# WiFi_SCH.net
KiCad netlist of a schematic drawn in Altium Designer
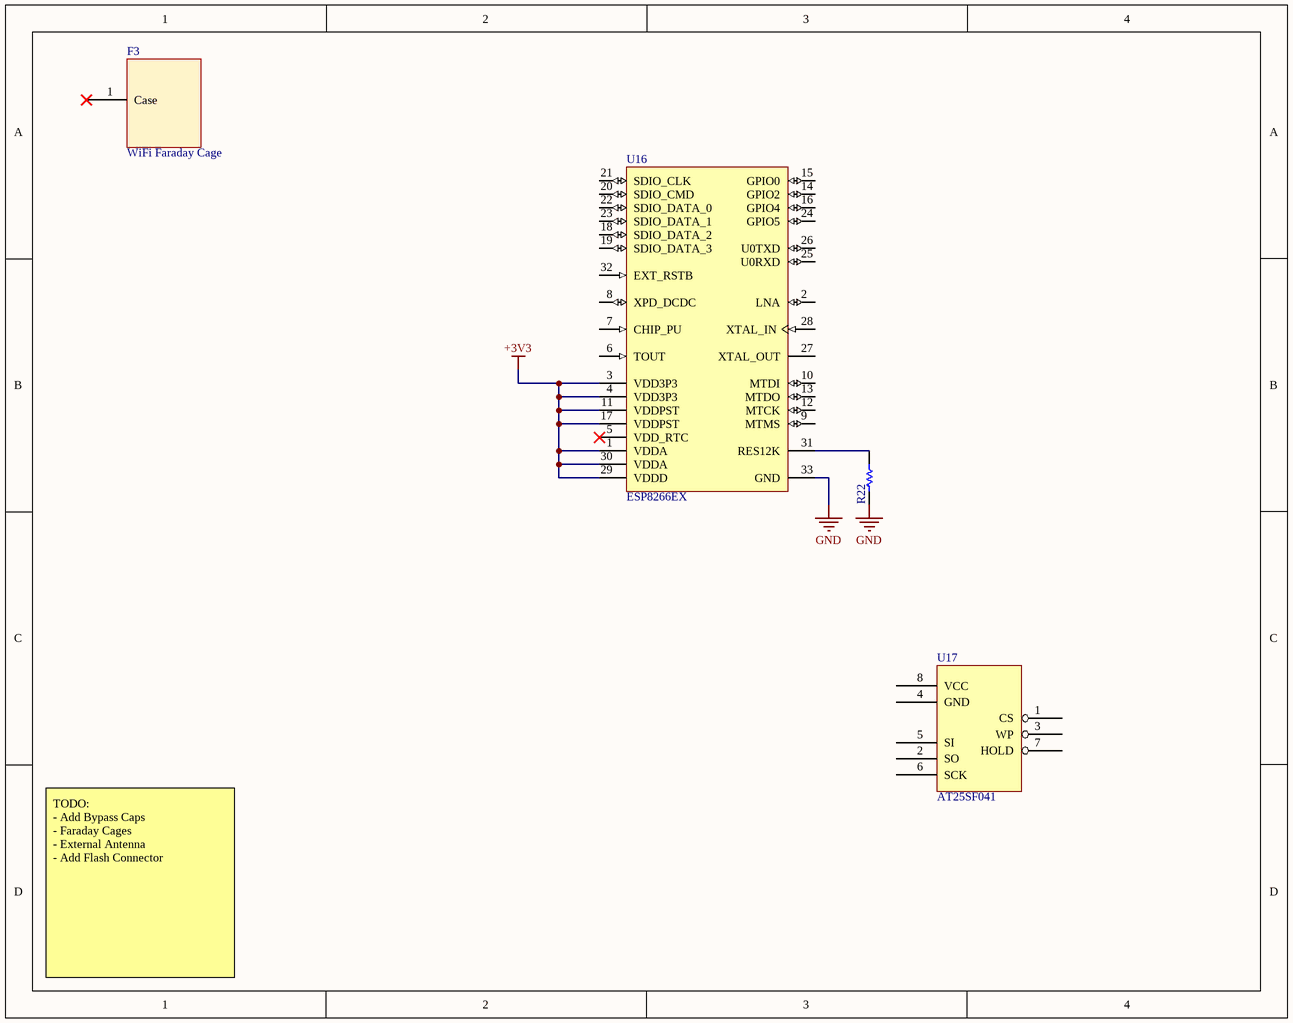
[diagram p0: WiFi_SCH.SchDoc]

(export (version "E")
  (design (tool "Eeschema 10.0.6"))
  (components
    (comp (ref "F3") (value "WiFi Faraday Cage") (libsource (lib "Copter") (part "FARADAY_CAGE")))
    (comp (ref "R22")
      (value "RES-2")
      (footprint "RES 0402")
      (fields (field (name "TOLERANCE") "1%"))
      (libsource (lib "Copter") (part "RES"))
    )
    (comp (ref "U16")
      (value "ESP8266EX")
      (footprint "ESFS-QFN-32_L")
      (description "Low-Power, Highly-Integrated Wi-Fi Solution, 2.5 to 3.6 V, 80 mA, -40 to 125 degC, 32-Pin QFN")
      (fields (field (name "MANUFACTURER") "Espressif Systems"))
      (libsource (lib "Altium Content Vault") (part "ESFS-ESP8266EX-32"))
    )
    (comp (ref "U17")
      (value "AT25SF041")
      (footprint "SOIC127P600X175-8N")
      (description "IC FLASH 4M SPI 104MHZ 8SOIC")
      (libsource (lib "Copter") (part "AT25SF041"))
    )
  )
  (nets
    (net (code "1") (name "+3V3") (class "Default")
      (node (ref "U16") (pin "1") (pinfunction "VDDA_1") (pintype "power_in"))
      (node (ref "U16") (pin "11") (pinfunction "VDDPST_11") (pintype "power_in"))
      (node (ref "U16") (pin "17") (pinfunction "VDDPST_17") (pintype "power_in"))
      (node (ref "U16") (pin "29") (pinfunction "VDDD_29") (pintype "power_in"))
      (node (ref "U16") (pin "3") (pinfunction "VDD3P3_3") (pintype "power_in"))
      (node (ref "U16") (pin "30") (pinfunction "VDDA_30") (pintype "power_in"))
      (node (ref "U16") (pin "4") (pinfunction "VDD3P3_4") (pintype "power_in"))
    )
    (net (code "2") (name "GND") (class "Default")
      (node (ref "R22") (pin "1") (pinfunction "1_1") (pintype "passive"))
      (node (ref "U16") (pin "33") (pinfunction "GND_33") (pintype "power_in"))
    )
    (net (code "3") (name "Net-(U16-RES12K)") (class "Default")
      (node (ref "R22") (pin "2") (pinfunction "2_2") (pintype "passive"))
      (node (ref "U16") (pin "31") (pinfunction "RES12K_31") (pintype "passive"))
    )
    (net (code "4") (name "unconnected-(F3-Case-Pad1)") (class "Default")
      (node (ref "F3") (pin "1") (pinfunction "Case_1") (pintype "passive+no_connect"))
    )
    (net (code "5") (name "unconnected-(U16-CHIP_PU-Pad7)") (class "Default")
      (node (ref "U16") (pin "7") (pinfunction "CHIP_PU_7") (pintype "input"))
    )
    (net (code "6") (name "unconnected-(U16-EXT_RSTB-Pad32)") (class "Default")
      (node (ref "U16") (pin "32") (pinfunction "EXT_RSTB_32") (pintype "input"))
    )
    (net (code "7") (name "unconnected-(U16-GPIO0-Pad15)") (class "Default")
      (node (ref "U16") (pin "15") (pinfunction "GPIO0_15") (pintype "bidirectional"))
    )
    (net (code "8") (name "unconnected-(U16-GPIO2-Pad14)") (class "Default")
      (node (ref "U16") (pin "14") (pinfunction "GPIO2_14") (pintype "bidirectional"))
    )
    (net (code "9") (name "unconnected-(U16-GPIO4-Pad16)") (class "Default")
      (node (ref "U16") (pin "16") (pinfunction "GPIO4_16") (pintype "bidirectional"))
    )
    (net (code "10") (name "unconnected-(U16-GPIO5-Pad24)") (class "Default")
      (node (ref "U16") (pin "24") (pinfunction "GPIO5_24") (pintype "bidirectional"))
    )
    (net (code "11") (name "unconnected-(U16-LNA-Pad2)") (class "Default")
      (node (ref "U16") (pin "2") (pinfunction "LNA_2") (pintype "bidirectional"))
    )
    (net (code "12") (name "unconnected-(U16-MTCK-Pad12)") (class "Default")
      (node (ref "U16") (pin "12") (pinfunction "MTCK_12") (pintype "bidirectional"))
    )
    (net (code "13") (name "unconnected-(U16-MTDI-Pad10)") (class "Default")
      (node (ref "U16") (pin "10") (pinfunction "MTDI_10") (pintype "bidirectional"))
    )
    (net (code "14") (name "unconnected-(U16-MTDO-Pad13)") (class "Default")
      (node (ref "U16") (pin "13") (pinfunction "MTDO_13") (pintype "bidirectional"))
    )
    (net (code "15") (name "unconnected-(U16-MTMS-Pad9)") (class "Default")
      (node (ref "U16") (pin "9") (pinfunction "MTMS_9") (pintype "bidirectional"))
    )
    (net (code "16") (name "unconnected-(U16-SDIO_CLK-Pad21)") (class "Default")
      (node (ref "U16") (pin "21") (pinfunction "SDIO_CLK_21") (pintype "bidirectional"))
    )
    (net (code "17") (name "unconnected-(U16-SDIO_CMD-Pad20)") (class "Default")
      (node (ref "U16") (pin "20") (pinfunction "SDIO_CMD_20") (pintype "bidirectional"))
    )
    (net (code "18") (name "unconnected-(U16-SDIO_DATA_0-Pad22)") (class "Default")
      (node (ref "U16") (pin "22") (pinfunction "SDIO_DATA_0_22") (pintype "bidirectional"))
    )
    (net (code "19") (name "unconnected-(U16-SDIO_DATA_1-Pad23)") (class "Default")
      (node (ref "U16") (pin "23") (pinfunction "SDIO_DATA_1_23") (pintype "bidirectional"))
    )
    (net (code "20") (name "unconnected-(U16-SDIO_DATA_2-Pad18)") (class "Default")
      (node (ref "U16") (pin "18") (pinfunction "SDIO_DATA_2_18") (pintype "bidirectional"))
    )
    (net (code "21") (name "unconnected-(U16-SDIO_DATA_3-Pad19)") (class "Default")
      (node (ref "U16") (pin "19") (pinfunction "SDIO_DATA_3_19") (pintype "bidirectional"))
    )
    (net (code "22") (name "unconnected-(U16-TOUT-Pad6)") (class "Default")
      (node (ref "U16") (pin "6") (pinfunction "TOUT_6") (pintype "input"))
    )
    (net (code "23") (name "unconnected-(U16-U0RXD-Pad25)") (class "Default")
      (node (ref "U16") (pin "25") (pinfunction "U0RXD_25") (pintype "bidirectional"))
    )
    (net (code "24") (name "unconnected-(U16-U0TXD-Pad26)") (class "Default")
      (node (ref "U16") (pin "26") (pinfunction "U0TXD_26") (pintype "bidirectional"))
    )
    (net (code "25") (name "unconnected-(U16-VDD_RTC-Pad5)") (class "Default")
      (node (ref "U16") (pin "5") (pinfunction "VDD_RTC_5") (pintype "power_in+no_connect"))
    )
    (net (code "26") (name "unconnected-(U16-XPD_DCDC-Pad8)") (class "Default")
      (node (ref "U16") (pin "8") (pinfunction "XPD_DCDC_8") (pintype "bidirectional"))
    )
    (net (code "27") (name "unconnected-(U16-XTAL_IN-Pad28)") (class "Default")
      (node (ref "U16") (pin "28") (pinfunction "XTAL_IN_28") (pintype "input"))
    )
    (net (code "28") (name "unconnected-(U16-XTAL_OUT-Pad27)") (class "Default")
      (node (ref "U16") (pin "27") (pinfunction "XTAL_OUT_27") (pintype "passive"))
    )
    (net (code "29") (name "unconnected-(U17-CS-Pad1)") (class "Default")
      (node (ref "U17") (pin "1") (pinfunction "CS_1") (pintype "passive"))
    )
    (net (code "30") (name "unconnected-(U17-GND-Pad4)") (class "Default")
      (node (ref "U17") (pin "4") (pinfunction "GND_4") (pintype "passive"))
    )
    (net (code "31") (name "unconnected-(U17-HOLD-Pad7)") (class "Default")
      (node (ref "U17") (pin "7") (pinfunction "HOLD_7") (pintype "passive"))
    )
    (net (code "32") (name "unconnected-(U17-SCK-Pad6)") (class "Default")
      (node (ref "U17") (pin "6") (pinfunction "SCK_6") (pintype "passive"))
    )
    (net (code "33") (name "unconnected-(U17-SI-Pad5)") (class "Default")
      (node (ref "U17") (pin "5") (pinfunction "SI_5") (pintype "passive"))
    )
    (net (code "34") (name "unconnected-(U17-SO-Pad2)") (class "Default")
      (node (ref "U17") (pin "2") (pinfunction "SO_2") (pintype "passive"))
    )
    (net (code "35") (name "unconnected-(U17-VCC-Pad8)") (class "Default")
      (node (ref "U17") (pin "8") (pinfunction "VCC_8") (pintype "passive"))
    )
    (net (code "36") (name "unconnected-(U17-WP-Pad3)") (class "Default")
      (node (ref "U17") (pin "3") (pinfunction "WP_3") (pintype "passive"))
    )
  )
)
